# Candunio.net
KiCad netlist of a schematic drawn in Altium Designer
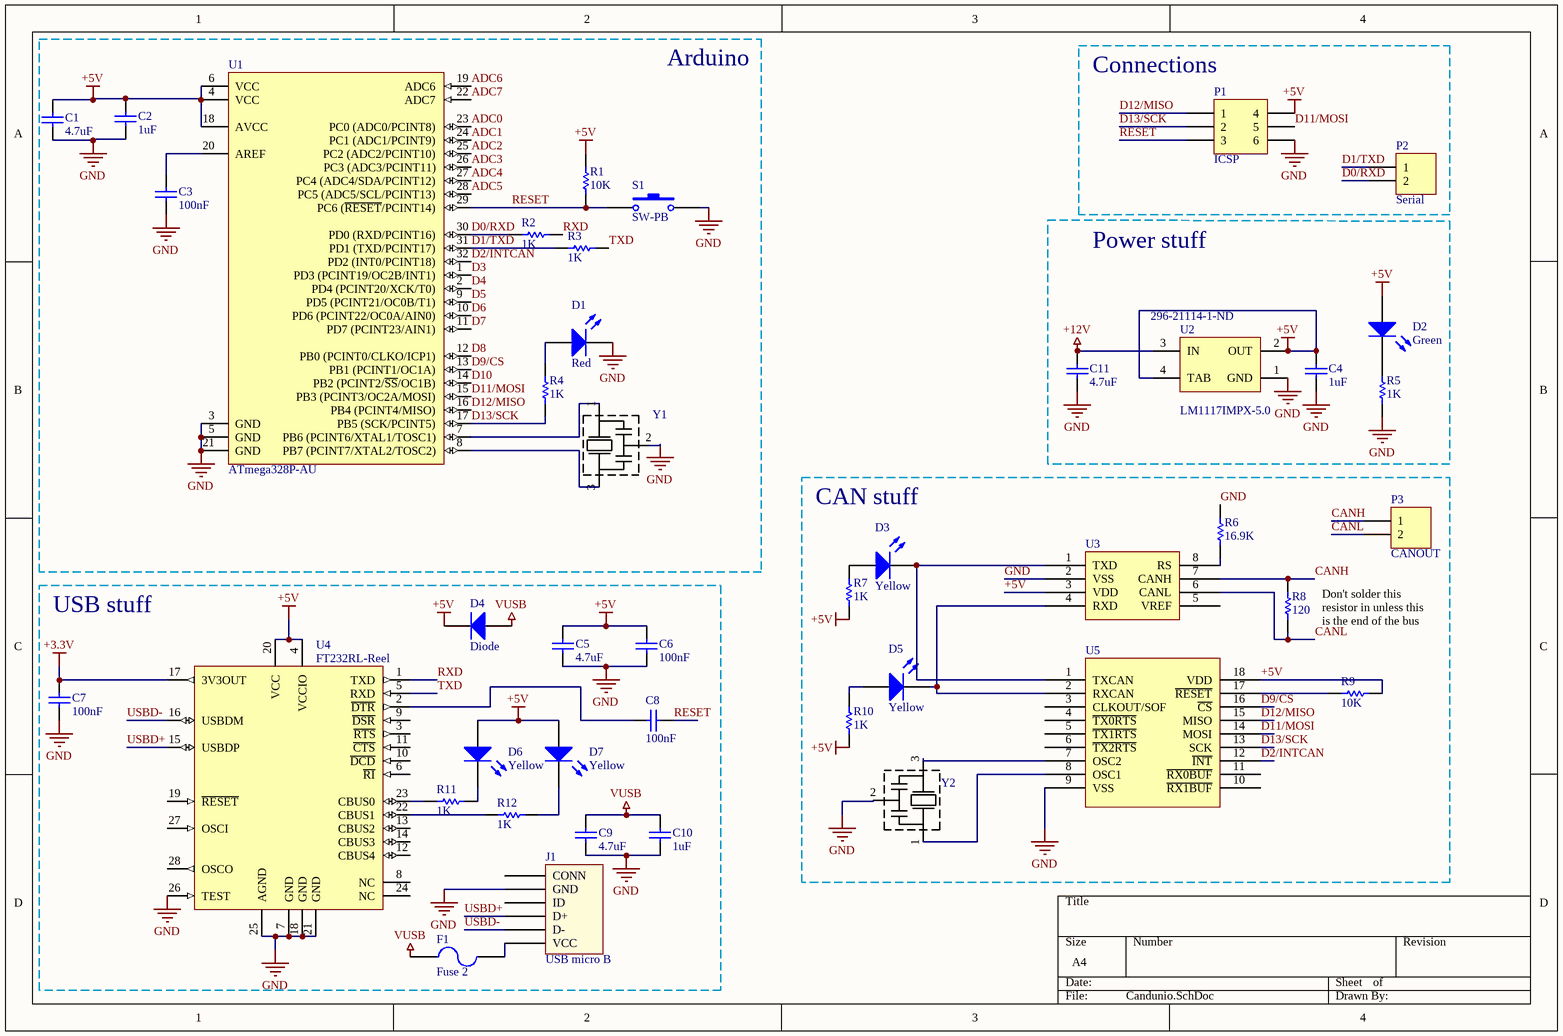
[diagram p0: Candunio.SchDoc]

(export (version "E")
  (design (tool "Eeschema 10.0.6"))
  (components
    (comp (ref "C1")
      (value "4.7uF")
      (footprint "CAPC3216X170N")
      (description "Capacitor (Semiconductor SIM Model)")
      (fields
        (field (name "MANUFACTURER") "Murata")
        (field (name "MANUFACTURER PART NUMBER") "GRM31MR71H105KA88L")
        (field (name "PUBLISHER") "Altium Limited")
      )
      (libsource (lib "Candunio v2018_7_27") (part "Cap Semi"))
    )
    (comp (ref "C2")
      (value "1uF")
      (footprint "CAPC3216X170N")
      (description "Capacitor (Semiconductor SIM Model)")
      (fields
        (field (name "MANUFACTURER") "Murata")
        (field (name "MANUFACTURER PART NUMBER") "GRM31MR71H105KA88L")
        (field (name "PUBLISHER") "Altium Limited")
      )
      (libsource (lib "Candunio v2018_7_27") (part "Cap Semi"))
    )
    (comp (ref "C3")
      (value "100nF")
      (footprint "CAPC3216X170N")
      (description "Capacitor (Semiconductor SIM Model)")
      (fields
        (field (name "MANUFACTURER") "Murata")
        (field (name "MANUFACTURER PART NUMBER") "GRM31MR71H105KA88L")
        (field (name "PUBLISHER") "Altium Limited")
      )
      (libsource (lib "Candunio v2018_7_27") (part "Cap Semi"))
    )
    (comp (ref "C4")
      (value "1uF")
      (footprint "CAPC3216X170N")
      (description "Capacitor (Semiconductor SIM Model)")
      (fields
        (field (name "MANUFACTURER") "Murata")
        (field (name "MANUFACTURER PART NUMBER") "GRM31MR71H105KA88L")
        (field (name "PUBLISHER") "Altium Limited")
      )
      (libsource (lib "Candunio v2018_7_27") (part "Cap Semi"))
    )
    (comp (ref "C5")
      (value "4.7uF")
      (footprint "CAPC3216X170N")
      (description "Capacitor (Semiconductor SIM Model)")
      (fields
        (field (name "MANUFACTURER") "Murata")
        (field (name "MANUFACTURER PART NUMBER") "GRM31MR71H105KA88L")
        (field (name "PUBLISHER") "Altium Limited")
      )
      (libsource (lib "Candunio v2018_7_27") (part "Cap Semi"))
    )
    (comp (ref "C6")
      (value "100nF")
      (footprint "CAPC3216X170N")
      (description "Capacitor (Semiconductor SIM Model)")
      (fields
        (field (name "MANUFACTURER") "Murata")
        (field (name "MANUFACTURER PART NUMBER") "GRM31MR71H105KA88L")
        (field (name "PUBLISHER") "Altium Limited")
      )
      (libsource (lib "Candunio v2018_7_27") (part "Cap Semi"))
    )
    (comp (ref "C7")
      (value "100nF")
      (footprint "CAPC3216X170N")
      (description "Capacitor (Semiconductor SIM Model)")
      (fields
        (field (name "MANUFACTURER") "Murata")
        (field (name "MANUFACTURER PART NUMBER") "GRM31MR71H105KA88L")
        (field (name "PUBLISHER") "Altium Limited")
      )
      (libsource (lib "Candunio v2018_7_27") (part "Cap Semi"))
    )
    (comp (ref "C8")
      (value "100nF")
      (footprint "CAPC3216X170N")
      (description "Capacitor (Semiconductor SIM Model)")
      (fields
        (field (name "MANUFACTURER") "Murata")
        (field (name "MANUFACTURER PART NUMBER") "GRM31MR71H105KA88L")
        (field (name "PUBLISHER") "Altium Limited")
      )
      (libsource (lib "Candunio v2018_7_27") (part "Cap Semi"))
    )
    (comp (ref "C9")
      (value "4.7uF")
      (footprint "CAPC3216X170N")
      (description "Capacitor (Semiconductor SIM Model)")
      (fields
        (field (name "MANUFACTURER") "Murata")
        (field (name "MANUFACTURER PART NUMBER") "GRM31MR71H105KA88L")
        (field (name "PUBLISHER") "Altium Limited")
      )
      (libsource (lib "Candunio v2018_7_27") (part "Cap Semi"))
    )
    (comp (ref "C10")
      (value "1uF")
      (footprint "CAPC3216X170N")
      (description "Capacitor (Semiconductor SIM Model)")
      (fields
        (field (name "MANUFACTURER") "Murata")
        (field (name "MANUFACTURER PART NUMBER") "GRM31MR71H105KA88L")
        (field (name "PUBLISHER") "Altium Limited")
      )
      (libsource (lib "Candunio v2018_7_27") (part "Cap Semi"))
    )
    (comp (ref "C11")
      (value "4.7uF")
      (footprint "CAPC3216X170N")
      (description "Capacitor (Semiconductor SIM Model)")
      (fields
        (field (name "MANUFACTURER") "Murata")
        (field (name "MANUFACTURER PART NUMBER") "GRM31MR71H105KA88L")
        (field (name "PUBLISHER") "Altium Limited")
      )
      (libsource (lib "Candunio v2018_7_27") (part "Cap Semi"))
    )
    (comp (ref "D1")
      (value "Red")
      (footprint "LEDC3216X120NRED")
      (description "Typical RED, GREEN, YELLOW, AMBER GaAs LED")
      (fields
        (field (name "MANUFACTURER") "Broadcom Avago")
        (field (name "MANUFACTURER PART NUMBER") "HSMY-C150")
        (field (name "PUBLISHER") "Altium Limited")
      )
      (libsource (lib "Miscellaneous Devices") (part "LED2"))
    )
    (comp (ref "D2")
      (value "Green")
      (footprint "LEDC3216X120NGRN")
      (description "Typical RED, GREEN, YELLOW, AMBER GaAs LED")
      (fields
        (field (name "MANUFACTURER") "Broadcom Avago")
        (field (name "MANUFACTURER PART NUMBER") "HSMG-C150")
        (field (name "PUBLISHER") "Altium Limited")
      )
      (libsource (lib "Miscellaneous Devices") (part "LED2"))
    )
    (comp (ref "D3")
      (value "Yellow")
      (footprint "LEDC3216X120NYEL")
      (description "Typical RED, GREEN, YELLOW, AMBER GaAs LED")
      (fields
        (field (name "MANUFACTURER") "Broadcom Avago")
        (field (name "MANUFACTURER PART NUMBER") "HSMY-C150")
        (field (name "PUBLISHER") "Altium Limited")
      )
      (libsource (lib "Miscellaneous Devices") (part "LED2"))
    )
    (comp (ref "D4")
      (value "Diode")
      (footprint "Integrated_Library1:DO-220AA")
      (description "Default Diode")
      (fields (field (name "PUBLISHER") "Altium Limited"))
      (libsource (lib "Miscellaneous Devices") (part "Diode"))
    )
    (comp (ref "D5")
      (value "Yellow")
      (footprint "LEDC3216X120NYEL")
      (description "Typical RED, GREEN, YELLOW, AMBER GaAs LED")
      (fields
        (field (name "MANUFACTURER") "Broadcom Avago")
        (field (name "MANUFACTURER PART NUMBER") "HSMY-C150")
        (field (name "PUBLISHER") "Altium Limited")
      )
      (libsource (lib "Miscellaneous Devices") (part "LED2"))
    )
    (comp (ref "D6")
      (value "Yellow")
      (footprint "LEDC3216X120NYEL")
      (description "Typical RED, GREEN, YELLOW, AMBER GaAs LED")
      (fields
        (field (name "MANUFACTURER") "Broadcom Avago")
        (field (name "MANUFACTURER PART NUMBER") "HSMY-C150")
        (field (name "PUBLISHER") "Altium Limited")
      )
      (libsource (lib "Miscellaneous Devices") (part "LED2"))
    )
    (comp (ref "D7")
      (value "Yellow")
      (footprint "LEDC3216X120NYEL")
      (description "Typical RED, GREEN, YELLOW, AMBER GaAs LED")
      (fields
        (field (name "MANUFACTURER") "Broadcom Avago")
        (field (name "MANUFACTURER PART NUMBER") "HSMY-C150")
        (field (name "PUBLISHER") "Altium Limited")
      )
      (libsource (lib "Miscellaneous Devices") (part "LED2"))
    )
    (comp (ref "F1")
      (value "Fuse 2")
      (footprint "FUSC4632X85N")
      (description "Fuse")
      (fields
        (field (name "PART NUMBER") "MF-MSMF050-2")
        (field (name "MANUFACTURER") "Bourns")
        (field (name "PUBLISHER") "Altium Limited")
      )
      (libsource (lib "Miscellaneous Devices") (part "Fuse 2"))
    )
    (comp (ref "J1")
      (value "USB micro B")
      (footprint "1050170001")
      (description "CONN SM TH USB MICRO MODIFIED FOR DRILL")
      (fields (field (name "PART NUMBER") "WM1399CT-ND"))
      (libsource (lib "electronpowered") (part "1050170001"))
    )
    (comp (ref "P1")
      (value "ICSP")
      (footprint "Pin Header 2x3 TH Pitch 2.54mm")
      (description "Header, 3-Pin, Dual row")
      (fields (field (name "PUBLISHER") "Altium Limited"))
      (libsource (lib "Miscellaneous Connectors") (part "Header 3X2A"))
    )
    (comp (ref "P2")
      (value "Serial")
      (footprint "Candunio v2018_7_16:Pin Header 1x2 TH Pitch 2.54mm")
      (description "Header, 2-Pin")
      (fields (field (name "PUBLISHER") "Altium Limited"))
      (libsource (lib "Miscellaneous Connectors") (part "Header 2"))
    )
    (comp (ref "P3")
      (value "CANOUT")
      (footprint "Candunio v2018_7_16:Pin Header 1x2 TH Pitch 2.54mm")
      (description "Header, 2-Pin")
      (fields (field (name "PUBLISHER") "Altium Limited"))
      (libsource (lib "Miscellaneous Connectors") (part "Header 2"))
    )
    (comp (ref "R1")
      (value "10K")
      (footprint "RESC3216X60N")
      (description "Resistor")
      (fields
        (field (name "MANUFACTURER") "Stackpole Electronics")
        (field (name "MANUFACTURER PART NUMBER") "RNCP1206FTD1K00")
      )
      (libsource (lib "Miscellaneous Devices") (part "Res1"))
    )
    (comp (ref "R2")
      (value "1K")
      (footprint "RESC3216X60N")
      (description "Resistor")
      (fields
        (field (name "MANUFACTURER") "Stackpole Electronics")
        (field (name "MANUFACTURER PART NUMBER") "RNCP1206FTD1K00")
      )
      (libsource (lib "Miscellaneous Devices") (part "Res1"))
    )
    (comp (ref "R3")
      (value "1K")
      (footprint "RESC3216X60N")
      (description "Resistor")
      (fields
        (field (name "MANUFACTURER") "Stackpole Electronics")
        (field (name "MANUFACTURER PART NUMBER") "RNCP1206FTD1K00")
      )
      (libsource (lib "Miscellaneous Devices") (part "Res1"))
    )
    (comp (ref "R4")
      (value "1K")
      (footprint "RESC3216X60N")
      (description "Resistor")
      (fields
        (field (name "MANUFACTURER") "Stackpole Electronics")
        (field (name "MANUFACTURER PART NUMBER") "RNCP1206FTD1K00")
      )
      (libsource (lib "Miscellaneous Devices") (part "Res1"))
    )
    (comp (ref "R5")
      (value "1K")
      (footprint "RESC3216X60N")
      (description "Resistor")
      (fields
        (field (name "MANUFACTURER") "Stackpole Electronics")
        (field (name "MANUFACTURER PART NUMBER") "RNCP1206FTD1K00")
      )
      (libsource (lib "Miscellaneous Devices") (part "Res1"))
    )
    (comp (ref "R6")
      (value "16.9K")
      (footprint "RESC3216X60N")
      (description "Resistor")
      (fields
        (field (name "MANUFACTURER") "TE Connectivity Holsworthy")
        (field (name "MANUFACTURER PART NUMBER") "CRGH1206F16K9")
      )
      (libsource (lib "Miscellaneous Devices") (part "Res1"))
    )
    (comp (ref "R7")
      (value "1K")
      (footprint "RESC3216X60N")
      (description "Resistor")
      (fields
        (field (name "MANUFACTURER") "Stackpole Electronics")
        (field (name "MANUFACTURER PART NUMBER") "RNCP1206FTD1K00")
      )
      (libsource (lib "Miscellaneous Devices") (part "Res1"))
    )
    (comp (ref "R8")
      (value "120")
      (footprint "RESC3216X60N")
      (description "Resistor")
      (fields
        (field (name "MANUFACTURER") "Vishay")
        (field (name "MANUFACTURER PART NUMBER") "CRCW1206120RFKEAHP")
      )
      (libsource (lib "Miscellaneous Devices") (part "Res1"))
    )
    (comp (ref "R9")
      (value "10K")
      (footprint "RESC3216X60N")
      (description "Resistor")
      (fields
        (field (name "MANUFACTURER") "Stackpole Electronics")
        (field (name "MANUFACTURER PART NUMBER") "RNCP1206FTD10K0")
      )
      (libsource (lib "Miscellaneous Devices") (part "Res1"))
    )
    (comp (ref "R10")
      (value "1K")
      (footprint "RESC3216X60N")
      (description "Resistor")
      (fields
        (field (name "MANUFACTURER") "Stackpole Electronics")
        (field (name "MANUFACTURER PART NUMBER") "RNCP1206FTD1K00")
      )
      (libsource (lib "Miscellaneous Devices") (part "Res1"))
    )
    (comp (ref "R11")
      (value "1K")
      (footprint "RESC3216X60N")
      (description "Resistor")
      (fields
        (field (name "MANUFACTURER") "Stackpole Electronics")
        (field (name "MANUFACTURER PART NUMBER") "RNCP1206FTD1K00")
      )
      (libsource (lib "Miscellaneous Devices") (part "Res1"))
    )
    (comp (ref "R12")
      (value "1K")
      (footprint "RESC3216X60N")
      (description "Resistor")
      (fields
        (field (name "MANUFACTURER") "Stackpole Electronics")
        (field (name "MANUFACTURER PART NUMBER") "RNCP1206FTD1K00")
      )
      (libsource (lib "Miscellaneous Devices") (part "Res1"))
    )
    (comp (ref "S1")
      (value "SW-PB")
      (footprint "1206SMDswitch:SMDswitch_1206")
      (description "Switch")
      (fields
        (field (name "MANUFACTURER") "ITT C&K")
        (field (name "MANUFACTURER PART NUMBER") "KXT331LHS")
        (field (name "PUBLISHER") "Altium Limited")
      )
      (libsource (lib "Miscellaneous Devices") (part "SW-PB"))
    )
    (comp (ref "U1")
      (value "ATmega328P-AU")
      (footprint "QFP80P900X900X120-32N")
      (fields (field (name "PUBLISHER") "Altium Limited"))
      (libsource (lib "Atmel Microcontroller 8-Bit megaAVR") (part "ATmega328P-AU"))
    )
    (comp (ref "U2")
      (value "LM1117IMPX-5.0")
      (footprint "SOT230P700X180-4N")
      (description "800mA Low-Dropout Linear Regulator, 4-pin SOT-223")
      (fields
        (field (name "PARTNUMBER") "LM1117IMPX-5.0/NOPBCT-ND")
        (field (name "MANUFACTURER") "National Semiconductor")
        (field (name "SUPPLIER PART NUMBER") "296-21114-1-ND")
        (field (name "PUBLISHER") "Altium Limited")
      )
      (libsource (lib "NSC LDO") (part "LM1117IMPX-5.0"))
    )
    (comp (ref "U3")
      (value "MCP2551-E/SN")
      (footprint "SOIC127P600X175-8N")
      (description "SOIC")
      (libsource (lib "AMSComponents") (part "MCP2551-E/SN"))
    )
    (comp (ref "U4")
      (value "FT232RL-Reel")
      (footprint "SOP65P780X200-28N")
      (description "USB UART Asynchronous Serial Data Transfer Chip, SSOP-28, Tape and Reel")
      (fields
        (field (name "MANUFACTURER") "FTDI")
        (field (name "MANUFACTURER PART NUMBER") "FT232RL-REEL")
        (field (name "PUBLISHER") "Altium Limited")
      )
      (libsource (lib "FTDI Communication UART") (part "FT232RL-Reel"))
    )
    (comp (ref "U5")
      (value "MCP2515-E/ST")
      (footprint "SOIC127P1030X265-18N")
      (description "SOIC")
      (libsource (lib "AMSComponents") (part "MCP2515-E/ST"))
    )
    (comp (ref "Y1")
      (value "CSTCE16M0V53-R0")
      (footprint "CSTCE_G")
      (fields
        (field (name "MANUFACTURER") "Murata")
        (field (name "MANUFACTURER PART NUMBER") "CSTCE16M0V53C-R0")
        (field (name "TOLERANCE") "0.5%")
      )
      (libsource (lib "AMSComponents") (part "CSTCE16M0V53-R0"))
    )
    (comp (ref "Y2")
      (value "CSTCE16M0V53-R0")
      (footprint "CSTCE_G")
      (fields
        (field (name "MANUFACTURER") "Murata")
        (field (name "MANUFACTURER PART NUMBER") "CSTCE16M0V53C-R0")
        (field (name "TOLERANCE") "0.5%")
      )
      (libsource (lib "AMSComponents") (part "CSTCE16M0V53-R0"))
    )
  )
  (nets
    (net (code "1") (name "+3.3V") (class "Default")
      (node (ref "C7") (pin "2") (pinfunction "2_2") (pintype "passive"))
      (node (ref "U4") (pin "17") (pinfunction "3V3OUT_17") (pintype "output"))
    )
    (net (code "2") (name "+5V") (class "Default")
      (node (ref "C1") (pin "1") (pinfunction "1_1") (pintype "passive"))
      (node (ref "C2") (pin "2") (pinfunction "2_2") (pintype "passive"))
      (node (ref "C4") (pin "2") (pinfunction "2_2") (pintype "passive"))
      (node (ref "C5") (pin "2") (pinfunction "2_2") (pintype "passive"))
      (node (ref "C6") (pin "2") (pinfunction "2_2") (pintype "passive"))
      (node (ref "D2") (pin "1") (pinfunction "A_1") (pintype "passive"))
      (node (ref "D4") (pin "1") (pinfunction "K_1") (pintype "passive"))
      (node (ref "D6") (pin "1") (pinfunction "A_1") (pintype "passive"))
      (node (ref "D7") (pin "1") (pinfunction "A_1") (pintype "passive"))
      (node (ref "P1") (pin "4") (pinfunction "4_4") (pintype "passive"))
      (node (ref "R1") (pin "1") (pinfunction "1_1") (pintype "passive"))
      (node (ref "R10") (pin "2") (pinfunction "2_2") (pintype "passive"))
      (node (ref "R7") (pin "1") (pinfunction "1_1") (pintype "passive"))
      (node (ref "R9") (pin "2") (pinfunction "2_2") (pintype "passive"))
      (node (ref "U1") (pin "18") (pinfunction "AVCC_18") (pintype "power_in"))
      (node (ref "U1") (pin "4") (pinfunction "VCC_4") (pintype "power_in"))
      (node (ref "U1") (pin "6") (pinfunction "VCC_6") (pintype "power_in"))
      (node (ref "U2") (pin "2") (pinfunction "OUT_2") (pintype "power_in"))
      (node (ref "U2") (pin "4") (pinfunction "TAB_4") (pintype "power_in"))
      (node (ref "U3") (pin "3") (pinfunction "VDD_3") (pintype "passive"))
      (node (ref "U4") (pin "20") (pinfunction "VCC_20") (pintype "power_in"))
      (node (ref "U4") (pin "4") (pinfunction "VCCIO_4") (pintype "power_in"))
      (node (ref "U5") (pin "18") (pinfunction "VDD_18") (pintype "passive"))
    )
    (net (code "3") (name "+12V") (class "Default")
      (node (ref "C11") (pin "2") (pinfunction "2_2") (pintype "passive"))
      (node (ref "U2") (pin "3") (pinfunction "IN_3") (pintype "power_in"))
    )
    (net (code "4") (name "/ADC0") (class "Default")
      (node (ref "U1") (pin "23") (pinfunction "PC0_(ADC0/PCINT8)_23") (pintype "bidirectional"))
    )
    (net (code "5") (name "/ADC1") (class "Default")
      (node (ref "U1") (pin "24") (pinfunction "PC1_(ADC1/PCINT9)_24") (pintype "bidirectional"))
    )
    (net (code "6") (name "/ADC2") (class "Default")
      (node (ref "U1") (pin "25") (pinfunction "PC2_(ADC2/PCINT10)_25") (pintype "bidirectional"))
    )
    (net (code "7") (name "/ADC3") (class "Default")
      (node (ref "U1") (pin "26") (pinfunction "PC3_(ADC3/PCINT11)_26") (pintype "bidirectional"))
    )
    (net (code "8") (name "/ADC4") (class "Default")
      (node (ref "U1") (pin "27") (pinfunction "PC4_(ADC4/SDA/PCINT12)_27") (pintype "bidirectional"))
    )
    (net (code "9") (name "/ADC5") (class "Default")
      (node (ref "U1") (pin "28") (pinfunction "PC5_(ADC5/SCL/PCINT13)_28") (pintype "bidirectional"))
    )
    (net (code "10") (name "/ADC6") (class "Default")
      (node (ref "U1") (pin "19") (pinfunction "ADC6_19") (pintype "input"))
    )
    (net (code "11") (name "/ADC7") (class "Default")
      (node (ref "U1") (pin "22") (pinfunction "ADC7_22") (pintype "input"))
    )
    (net (code "12") (name "/CANH") (class "Default")
      (node (ref "P3") (pin "1") (pinfunction "1_1") (pintype "passive"))
      (node (ref "R8") (pin "1") (pinfunction "1_1") (pintype "passive"))
      (node (ref "U3") (pin "7") (pinfunction "CANH_7") (pintype "passive"))
    )
    (net (code "13") (name "/CANL") (class "Default")
      (node (ref "P3") (pin "2") (pinfunction "2_2") (pintype "passive"))
      (node (ref "R8") (pin "2") (pinfunction "2_2") (pintype "passive"))
      (node (ref "U3") (pin "6") (pinfunction "CANL_6") (pintype "passive"))
    )
    (net (code "14") (name "/D0{slash}RXD") (class "Default")
      (node (ref "P2") (pin "2") (pinfunction "2_2") (pintype "passive"))
      (node (ref "R2") (pin "1") (pinfunction "1_1") (pintype "passive"))
      (node (ref "U1") (pin "30") (pinfunction "PD0_(RXD/PCINT16)_30") (pintype "bidirectional"))
    )
    (net (code "15") (name "/D1{slash}TXD") (class "Default")
      (node (ref "P2") (pin "1") (pinfunction "1_1") (pintype "passive"))
      (node (ref "R3") (pin "1") (pinfunction "1_1") (pintype "passive"))
      (node (ref "U1") (pin "31") (pinfunction "PD1_(TXD/PCINT17)_31") (pintype "bidirectional"))
    )
    (net (code "16") (name "/D2{slash}INTCAN") (class "Default")
      (node (ref "U1") (pin "32") (pinfunction "PD2_(INT0/PCINT18)_32") (pintype "bidirectional"))
      (node (ref "U5") (pin "12") (pinfunction "~{INT}_12") (pintype "passive"))
    )
    (net (code "17") (name "/D3") (class "Default")
      (node (ref "U1") (pin "1") (pinfunction "PD3_(PCINT19/OC2B/INT1)_1") (pintype "bidirectional"))
    )
    (net (code "18") (name "/D4") (class "Default")
      (node (ref "U1") (pin "2") (pinfunction "PD4_(PCINT20/XCK/T0)_2") (pintype "bidirectional"))
    )
    (net (code "19") (name "/D5") (class "Default")
      (node (ref "U1") (pin "9") (pinfunction "PD5_(PCINT21/OC0B/T1)_9") (pintype "bidirectional"))
    )
    (net (code "20") (name "/D6") (class "Default")
      (node (ref "U1") (pin "10") (pinfunction "PD6_(PCINT22/OC0A/AIN0)_10") (pintype "bidirectional"))
    )
    (net (code "21") (name "/D7") (class "Default")
      (node (ref "U1") (pin "11") (pinfunction "PD7_(PCINT23/AIN1)_11") (pintype "bidirectional"))
    )
    (net (code "22") (name "/D8") (class "Default")
      (node (ref "U1") (pin "12") (pinfunction "PB0_(PCINT0/CLKO/ICP1)_12") (pintype "bidirectional"))
    )
    (net (code "23") (name "/D9{slash}CS") (class "Default")
      (node (ref "U1") (pin "13") (pinfunction "PB1_(PCINT1/OC1A)_13") (pintype "bidirectional"))
      (node (ref "U5") (pin "16") (pinfunction "~{CS}_16") (pintype "passive"))
    )
    (net (code "24") (name "/D10") (class "Default")
      (node (ref "U1") (pin "14") (pinfunction "PB2_(PCINT2/~{SS}/OC1B)_14") (pintype "bidirectional"))
    )
    (net (code "25") (name "/D11{slash}MOSI") (class "Default")
      (node (ref "P1") (pin "5") (pinfunction "5_5") (pintype "passive"))
      (node (ref "U1") (pin "15") (pinfunction "PB3_(PCINT3/OC2A/MOSI)_15") (pintype "bidirectional"))
      (node (ref "U5") (pin "14") (pinfunction "MOSI_14") (pintype "passive"))
    )
    (net (code "26") (name "/D12{slash}MISO") (class "Default")
      (node (ref "P1") (pin "1") (pinfunction "1_1") (pintype "passive"))
      (node (ref "U1") (pin "16") (pinfunction "PB4_(PCINT4/MISO)_16") (pintype "bidirectional"))
      (node (ref "U5") (pin "15") (pinfunction "MISO_15") (pintype "passive"))
    )
    (net (code "27") (name "/D13{slash}SCK") (class "Default")
      (node (ref "P1") (pin "2") (pinfunction "2_2") (pintype "passive"))
      (node (ref "R4") (pin "2") (pinfunction "2_2") (pintype "passive"))
      (node (ref "U1") (pin "17") (pinfunction "PB5_(SCK/PCINT5)_17") (pintype "bidirectional"))
      (node (ref "U5") (pin "13") (pinfunction "SCK_13") (pintype "passive"))
    )
    (net (code "28") (name "/RESET") (class "Default")
      (node (ref "C8") (pin "2") (pinfunction "2_2") (pintype "passive"))
      (node (ref "P1") (pin "3") (pinfunction "3_3") (pintype "passive"))
      (node (ref "R1") (pin "2") (pinfunction "2_2") (pintype "passive"))
      (node (ref "S1") (pin "1") (pinfunction "1_1") (pintype "passive"))
      (node (ref "U1") (pin "29") (pinfunction "PC6_(~{RESET}/PCINT14)_29") (pintype "bidirectional"))
    )
    (net (code "29") (name "/RXD") (class "Default")
      (node (ref "R2") (pin "2") (pinfunction "2_2") (pintype "passive"))
      (node (ref "U4") (pin "1") (pinfunction "TXD_1") (pintype "output"))
    )
    (net (code "30") (name "/TXD") (class "Default")
      (node (ref "R3") (pin "2") (pinfunction "2_2") (pintype "passive"))
      (node (ref "U4") (pin "5") (pinfunction "RXD_5") (pintype "input"))
    )
    (net (code "31") (name "/USBD+") (class "Default")
      (node (ref "J1") (pin "3") (pinfunction "D+_3") (pintype "passive"))
      (node (ref "U4") (pin "15") (pinfunction "USBDP_15") (pintype "bidirectional"))
    )
    (net (code "32") (name "/USBD-") (class "Default")
      (node (ref "J1") (pin "2") (pinfunction "D-_2") (pintype "passive"))
      (node (ref "U4") (pin "16") (pinfunction "USBDM_16") (pintype "bidirectional"))
    )
    (net (code "33") (name "GND") (class "Default")
      (node (ref "C1") (pin "2") (pinfunction "2_2") (pintype "passive"))
      (node (ref "C10") (pin "1") (pinfunction "1_1") (pintype "passive"))
      (node (ref "C11") (pin "1") (pinfunction "1_1") (pintype "passive"))
      (node (ref "C2") (pin "1") (pinfunction "1_1") (pintype "passive"))
      (node (ref "C3") (pin "1") (pinfunction "1_1") (pintype "passive"))
      (node (ref "C4") (pin "1") (pinfunction "1_1") (pintype "passive"))
      (node (ref "C5") (pin "1") (pinfunction "1_1") (pintype "passive"))
      (node (ref "C6") (pin "1") (pinfunction "1_1") (pintype "passive"))
      (node (ref "C7") (pin "1") (pinfunction "1_1") (pintype "passive"))
      (node (ref "C9") (pin "1") (pinfunction "1_1") (pintype "passive"))
      (node (ref "D1") (pin "2") (pinfunction "K_2") (pintype "passive"))
      (node (ref "J1") (pin "5") (pinfunction "GND_5") (pintype "passive"))
      (node (ref "P1") (pin "6") (pinfunction "6_6") (pintype "passive"))
      (node (ref "R5") (pin "2") (pinfunction "2_2") (pintype "passive"))
      (node (ref "R6") (pin "1") (pinfunction "1_1") (pintype "passive"))
      (node (ref "S1") (pin "2") (pinfunction "2_2") (pintype "passive"))
      (node (ref "U1") (pin "21") (pinfunction "GND_21") (pintype "power_in"))
      (node (ref "U1") (pin "3") (pinfunction "GND_3") (pintype "power_in"))
      (node (ref "U1") (pin "5") (pinfunction "GND_5") (pintype "power_in"))
      (node (ref "U2") (pin "1") (pinfunction "GND_1") (pintype "power_in"))
      (node (ref "U3") (pin "2") (pinfunction "VSS_2") (pintype "passive"))
      (node (ref "U4") (pin "18") (pinfunction "GND_18") (pintype "power_in"))
      (node (ref "U4") (pin "21") (pinfunction "GND_21") (pintype "power_in"))
      (node (ref "U4") (pin "25") (pinfunction "AGND_25") (pintype "power_in"))
      (node (ref "U4") (pin "26") (pinfunction "TEST_26") (pintype "input"))
      (node (ref "U4") (pin "7") (pinfunction "GND_7") (pintype "power_in"))
      (node (ref "U5") (pin "9") (pinfunction "VSS_9") (pintype "passive"))
      (node (ref "Y1") (pin "2") (pinfunction "2_2") (pintype "passive"))
      (node (ref "Y2") (pin "2") (pinfunction "2_2") (pintype "passive"))
    )
    (net (code "34") (name "Net-(D1-A)") (class "Default")
      (node (ref "D1") (pin "1") (pinfunction "A_1") (pintype "passive"))
      (node (ref "R4") (pin "1") (pinfunction "1_1") (pintype "passive"))
    )
    (net (code "35") (name "Net-(D2-K)") (class "Default")
      (node (ref "D2") (pin "2") (pinfunction "K_2") (pintype "passive"))
      (node (ref "R5") (pin "1") (pinfunction "1_1") (pintype "passive"))
    )
    (net (code "36") (name "Net-(D3-A)") (class "Default")
      (node (ref "D3") (pin "1") (pinfunction "A_1") (pintype "passive"))
      (node (ref "R7") (pin "2") (pinfunction "2_2") (pintype "passive"))
    )
    (net (code "37") (name "Net-(D3-K)") (class "Default")
      (node (ref "D3") (pin "2") (pinfunction "K_2") (pintype "passive"))
      (node (ref "U3") (pin "1") (pinfunction "TXD_1") (pintype "passive"))
      (node (ref "U5") (pin "1") (pinfunction "TXCAN_1") (pintype "passive"))
    )
    (net (code "38") (name "Net-(D5-A)") (class "Default")
      (node (ref "D5") (pin "1") (pinfunction "A_1") (pintype "passive"))
      (node (ref "R10") (pin "1") (pinfunction "1_1") (pintype "passive"))
    )
    (net (code "39") (name "Net-(D5-K)") (class "Default")
      (node (ref "D5") (pin "2") (pinfunction "K_2") (pintype "passive"))
      (node (ref "U3") (pin "4") (pinfunction "RXD_4") (pintype "passive"))
      (node (ref "U5") (pin "2") (pinfunction "RXCAN_2") (pintype "passive"))
    )
    (net (code "40") (name "Net-(D6-K)") (class "Default")
      (node (ref "D6") (pin "2") (pinfunction "K_2") (pintype "passive"))
      (node (ref "R11") (pin "2") (pinfunction "2_2") (pintype "passive"))
    )
    (net (code "41") (name "Net-(D7-K)") (class "Default")
      (node (ref "D7") (pin "2") (pinfunction "K_2") (pintype "passive"))
      (node (ref "R12") (pin "2") (pinfunction "2_2") (pintype "passive"))
    )
    (net (code "42") (name "Net-(J1-VCC)") (class "Default")
      (node (ref "F1") (pin "2") (pinfunction "2_2") (pintype "passive"))
      (node (ref "J1") (pin "1") (pinfunction "VCC_1") (pintype "passive"))
    )
    (net (code "43") (name "Net-(U1-AREF)") (class "Default")
      (node (ref "C3") (pin "2") (pinfunction "2_2") (pintype "passive"))
      (node (ref "U1") (pin "20") (pinfunction "AREF_20") (pintype "passive"))
    )
    (net (code "44") (name "Net-(U1-PB6_(PCINT6{slash}XTAL1{slash}TOSC1))") (class "Default")
      (node (ref "U1") (pin "7") (pinfunction "PB6_(PCINT6/XTAL1/TOSC1)_7") (pintype "bidirectional"))
      (node (ref "Y1") (pin "1") (pinfunction "1_1") (pintype "passive"))
    )
    (net (code "45") (name "Net-(U1-PB7_(PCINT7{slash}XTAL2{slash}TOSC2))") (class "Default")
      (node (ref "U1") (pin "8") (pinfunction "PB7_(PCINT7/XTAL2/TOSC2)_8") (pintype "bidirectional"))
      (node (ref "Y1") (pin "3") (pinfunction "3_3") (pintype "passive"))
    )
    (net (code "46") (name "Net-(U3-RS)") (class "Default")
      (node (ref "R6") (pin "2") (pinfunction "2_2") (pintype "passive"))
      (node (ref "U3") (pin "8") (pinfunction "RS_8") (pintype "passive"))
    )
    (net (code "47") (name "Net-(U4-CBUS0)") (class "Default")
      (node (ref "R11") (pin "1") (pinfunction "1_1") (pintype "passive"))
      (node (ref "U4") (pin "23") (pinfunction "CBUS0_23") (pintype "bidirectional"))
    )
    (net (code "48") (name "Net-(U4-CBUS1)") (class "Default")
      (node (ref "R12") (pin "1") (pinfunction "1_1") (pintype "passive"))
      (node (ref "U4") (pin "22") (pinfunction "CBUS1_22") (pintype "bidirectional"))
    )
    (net (code "49") (name "Net-(U4-~{DTR})") (class "Default")
      (node (ref "C8") (pin "1") (pinfunction "1_1") (pintype "passive"))
      (node (ref "U4") (pin "2") (pinfunction "~{DTR}_2") (pintype "output"))
    )
    (net (code "50") (name "Net-(U5-OSC1)") (class "Default")
      (node (ref "U5") (pin "8") (pinfunction "OSC1_8") (pintype "passive"))
      (node (ref "Y2") (pin "1") (pinfunction "1_1") (pintype "passive"))
    )
    (net (code "51") (name "Net-(U5-OSC2)") (class "Default")
      (node (ref "U5") (pin "7") (pinfunction "OSC2_7") (pintype "passive"))
      (node (ref "Y2") (pin "3") (pinfunction "3_3") (pintype "passive"))
    )
    (net (code "52") (name "Net-(U5-~{RESET})") (class "Default")
      (node (ref "R9") (pin "1") (pinfunction "1_1") (pintype "passive"))
      (node (ref "U5") (pin "17") (pinfunction "~{RESET}_17") (pintype "passive"))
    )
    (net (code "53") (name "VUSB") (class "Default")
      (node (ref "C10") (pin "2") (pinfunction "2_2") (pintype "passive"))
      (node (ref "C9") (pin "2") (pinfunction "2_2") (pintype "passive"))
      (node (ref "D4") (pin "2") (pinfunction "A_2") (pintype "passive"))
      (node (ref "F1") (pin "1") (pinfunction "1_1") (pintype "passive"))
    )
    (net (code "54") (name "unconnected-(J1-CONN-Pad0)") (class "Default")
      (node (ref "J1") (pin "0") (pinfunction "CONN_0") (pintype "passive"))
    )
    (net (code "55") (name "unconnected-(J1-ID-Pad4)") (class "Default")
      (node (ref "J1") (pin "4") (pinfunction "ID_4") (pintype "passive"))
    )
    (net (code "56") (name "unconnected-(U3-VREF-Pad5)") (class "Default")
      (node (ref "U3") (pin "5") (pinfunction "VREF_5") (pintype "passive"))
    )
    (net (code "57") (name "unconnected-(U4-CBUS2-Pad13)") (class "Default")
      (node (ref "U4") (pin "13") (pinfunction "CBUS2_13") (pintype "bidirectional"))
    )
    (net (code "58") (name "unconnected-(U4-CBUS3-Pad14)") (class "Default")
      (node (ref "U4") (pin "14") (pinfunction "CBUS3_14") (pintype "bidirectional"))
    )
    (net (code "59") (name "unconnected-(U4-CBUS4-Pad12)") (class "Default")
      (node (ref "U4") (pin "12") (pinfunction "CBUS4_12") (pintype "bidirectional"))
    )
    (net (code "60") (name "unconnected-(U4-NC-Pad8)") (class "Default")
      (node (ref "U4") (pin "8") (pinfunction "NC_8") (pintype "passive"))
    )
    (net (code "61") (name "unconnected-(U4-NC-Pad24)") (class "Default")
      (node (ref "U4") (pin "24") (pinfunction "NC_24") (pintype "passive"))
    )
    (net (code "62") (name "unconnected-(U4-OSCI-Pad27)") (class "Default")
      (node (ref "U4") (pin "27") (pinfunction "OSCI_27") (pintype "input"))
    )
    (net (code "63") (name "unconnected-(U4-OSCO-Pad28)") (class "Default")
      (node (ref "U4") (pin "28") (pinfunction "OSCO_28") (pintype "output"))
    )
    (net (code "64") (name "unconnected-(U4-~{CTS}-Pad11)") (class "Default")
      (node (ref "U4") (pin "11") (pinfunction "~{CTS}_11") (pintype "input"))
    )
    (net (code "65") (name "unconnected-(U4-~{DCD}-Pad10)") (class "Default")
      (node (ref "U4") (pin "10") (pinfunction "~{DCD}_10") (pintype "input"))
    )
    (net (code "66") (name "unconnected-(U4-~{DSR}-Pad9)") (class "Default")
      (node (ref "U4") (pin "9") (pinfunction "~{DSR}_9") (pintype "input"))
    )
    (net (code "67") (name "unconnected-(U4-~{RESET}-Pad19)") (class "Default")
      (node (ref "U4") (pin "19") (pinfunction "~{RESET}_19") (pintype "input"))
    )
    (net (code "68") (name "unconnected-(U4-~{RI}-Pad6)") (class "Default")
      (node (ref "U4") (pin "6") (pinfunction "~{RI}_6") (pintype "input"))
    )
    (net (code "69") (name "unconnected-(U4-~{RTS}-Pad3)") (class "Default")
      (node (ref "U4") (pin "3") (pinfunction "~{RTS}_3") (pintype "output"))
    )
    (net (code "70") (name "unconnected-(U5-CLKOUT{slash}SOF-Pad3)") (class "Default")
      (node (ref "U5") (pin "3") (pinfunction "CLKOUT/SOF_3") (pintype "passive"))
    )
    (net (code "71") (name "unconnected-(U5-~{RX0BUF}-Pad11)") (class "Default")
      (node (ref "U5") (pin "11") (pinfunction "~{RX0BUF}_11") (pintype "passive"))
    )
    (net (code "72") (name "unconnected-(U5-~{RX1BUF}-Pad10)") (class "Default")
      (node (ref "U5") (pin "10") (pinfunction "~{RX1BUF}_10") (pintype "passive"))
    )
    (net (code "73") (name "unconnected-(U5-~{TX0RTS}-Pad4)") (class "Default")
      (node (ref "U5") (pin "4") (pinfunction "~{TX0RTS}_4") (pintype "passive"))
    )
    (net (code "74") (name "unconnected-(U5-~{TX1RTS}-Pad5)") (class "Default")
      (node (ref "U5") (pin "5") (pinfunction "~{TX1RTS}_5") (pintype "passive"))
    )
    (net (code "75") (name "unconnected-(U5-~{TX2RTS}-Pad6)") (class "Default")
      (node (ref "U5") (pin "6") (pinfunction "~{TX2RTS}_6") (pintype "passive"))
    )
  )
)
